# untitled.net
KiCad netlist of a schematic drawn in EAGLE
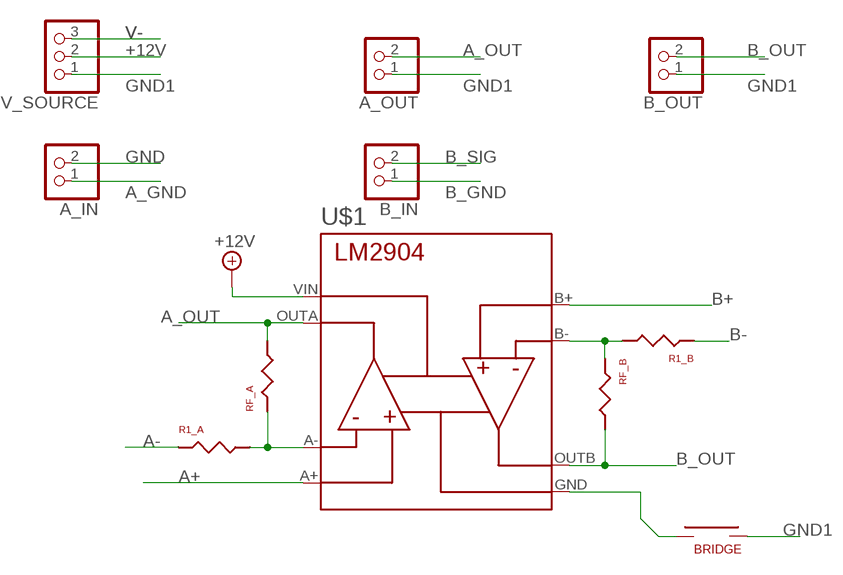
[diagram p0: schematic, sheet 1]

(export (version "E")
  (design (tool "Eeschema 10.0.6"))
  (components
    (comp (ref "A_IN")
      (value "PINHD-1X2")
      (footprint "eagle-import:1X02")
      (libsource (lib "eagle-import") (part "PINHD-1X2"))
    )
    (comp (ref "A_OUT")
      (value "PINHD-1X2")
      (footprint "eagle-import:1X02")
      (libsource (lib "eagle-import") (part "PINHD-1X2"))
    )
    (comp (ref "B_IN")
      (value "PINHD-1X2")
      (footprint "eagle-import:1X02")
      (libsource (lib "eagle-import") (part "PINHD-1X2"))
    )
    (comp (ref "B_OUT")
      (value "PINHD-1X2")
      (footprint "eagle-import:1X02")
      (libsource (lib "eagle-import") (part "PINHD-1X2"))
    )
    (comp (ref "R1_A")
      (value "RESISTOR")
      (footprint "eagle-import:RESISTOR")
      (libsource (lib "eagle-import") (part "RESISTOR"))
    )
    (comp (ref "R1_B")
      (value "RESISTOR")
      (footprint "eagle-import:RESISTOR")
      (libsource (lib "eagle-import") (part "RESISTOR"))
    )
    (comp (ref "RF_A")
      (value "RESISTOR")
      (footprint "eagle-import:RESISTOR")
      (libsource (lib "eagle-import") (part "RESISTOR"))
    )
    (comp (ref "RF_B")
      (value "RESISTOR")
      (footprint "eagle-import:RESISTOR")
      (libsource (lib "eagle-import") (part "RESISTOR"))
    )
    (comp (ref "U$1")
      (value "LM2904")
      (footprint "eagle-import:LM2904")
      (libsource (lib "eagle-import") (part "LM2904"))
    )
    (comp (ref "U$2")
      (value "BRIDGE")
      (footprint "eagle-import:BRIDGE")
      (libsource (lib "eagle-import") (part "BRIDGE"))
    )
    (comp (ref "V_SOURCE")
      (value "PINHD-1X3")
      (footprint "eagle-import:1X03")
      (libsource (lib "eagle-import") (part "PINHD-1X3"))
    )
  )
  (nets
    (net (code "1") (name "+12V") (class "Default")
      (node (ref "U$1") (pin "VIN") (pinfunction "P$7_VIN") (pintype "bidirectional"))
      (node (ref "V_SOURCE") (pin "2") (pinfunction "2_2") (pintype "passive"))
    )
    (net (code "2") (name "/A+") (class "Default")
      (node (ref "U$1") (pin "A+") (pinfunction "P$3_A+") (pintype "bidirectional"))
    )
    (net (code "3") (name "/A-") (class "Default")
      (node (ref "R1_A") (pin "P$1") (pinfunction "P$1_P$1") (pintype "bidirectional"))
    )
    (net (code "4") (name "/A_GND") (class "Default")
      (node (ref "A_IN") (pin "1") (pinfunction "1_1") (pintype "passive"))
    )
    (net (code "5") (name "/A_OUT") (class "Default")
      (node (ref "A_OUT") (pin "2") (pinfunction "2_2") (pintype "passive"))
      (node (ref "RF_A") (pin "P$2") (pinfunction "P$2_P$2") (pintype "bidirectional"))
      (node (ref "U$1") (pin "OUTA") (pinfunction "P$1_OUTA") (pintype "bidirectional"))
    )
    (net (code "6") (name "/B+") (class "Default")
      (node (ref "U$1") (pin "B+") (pinfunction "P$5_B+") (pintype "bidirectional"))
    )
    (net (code "7") (name "/B-") (class "Default")
      (node (ref "R1_B") (pin "P$1") (pinfunction "P$1_P$1") (pintype "bidirectional"))
    )
    (net (code "8") (name "/B_GND") (class "Default")
      (node (ref "B_IN") (pin "1") (pinfunction "1_1") (pintype "passive"))
    )
    (net (code "9") (name "/B_OUT") (class "Default")
      (node (ref "B_OUT") (pin "2") (pinfunction "2_2") (pintype "passive"))
      (node (ref "RF_B") (pin "P$2") (pinfunction "P$2_P$2") (pintype "bidirectional"))
      (node (ref "U$1") (pin "OUTB") (pinfunction "P$4_OUTB") (pintype "bidirectional"))
    )
    (net (code "10") (name "/B_SIG") (class "Default")
      (node (ref "B_IN") (pin "2") (pinfunction "2_2") (pintype "passive"))
    )
    (net (code "11") (name "/GND") (class "Default")
      (node (ref "A_IN") (pin "2") (pinfunction "2_2") (pintype "passive"))
    )
    (net (code "12") (name "/GND1") (class "Default")
      (node (ref "A_OUT") (pin "1") (pinfunction "1_1") (pintype "passive"))
      (node (ref "B_OUT") (pin "1") (pinfunction "1_1") (pintype "passive"))
      (node (ref "U$2") (pin "P$2") (pinfunction "P$2_P$2") (pintype "bidirectional"))
      (node (ref "V_SOURCE") (pin "1") (pinfunction "1_1") (pintype "passive"))
    )
    (net (code "13") (name "/V-") (class "Default")
      (node (ref "U$1") (pin "GND") (pinfunction "P$8_GND") (pintype "bidirectional"))
      (node (ref "U$2") (pin "P$1") (pinfunction "P$1_P$1") (pintype "bidirectional"))
      (node (ref "V_SOURCE") (pin "3") (pinfunction "3_3") (pintype "passive"))
    )
    (net (code "14") (name "Net-(U$1-P$2)") (class "Default")
      (node (ref "R1_A") (pin "P$2") (pinfunction "P$2_P$2") (pintype "bidirectional"))
      (node (ref "RF_A") (pin "P$1") (pinfunction "P$1_P$1") (pintype "bidirectional"))
      (node (ref "U$1") (pin "A-") (pinfunction "P$2_A-") (pintype "bidirectional"))
    )
    (net (code "15") (name "Net-(U$1-P$6)") (class "Default")
      (node (ref "R1_B") (pin "P$2") (pinfunction "P$2_P$2") (pintype "bidirectional"))
      (node (ref "RF_B") (pin "P$1") (pinfunction "P$1_P$1") (pintype "bidirectional"))
      (node (ref "U$1") (pin "B-") (pinfunction "P$6_B-") (pintype "bidirectional"))
    )
  )
)
